# humidity.net
KiCad netlist of a schematic drawn in EAGLE
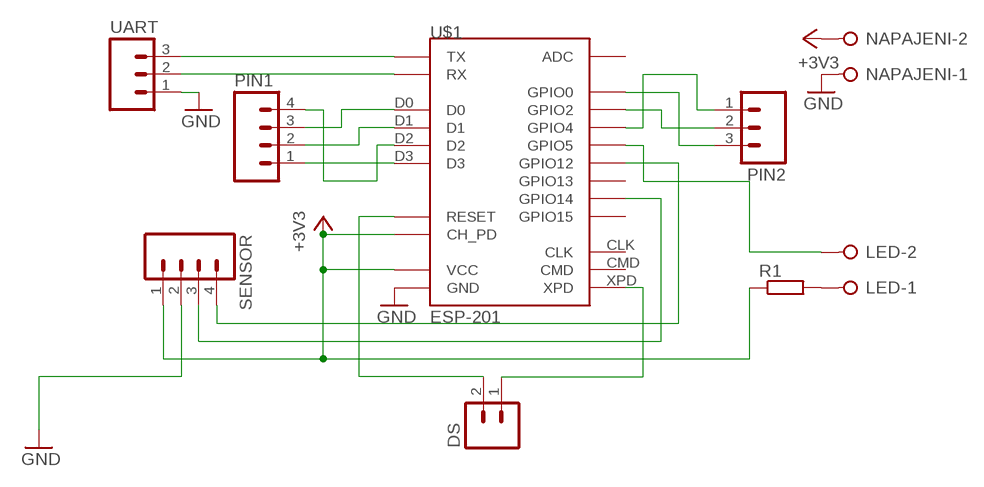
[diagram p0: schematic, sheet 1]

(export (version "E")
  (design (tool "Eeschema 10.0.6"))
  (components
    (comp (ref "DS")
      (value "M02")
      (footprint "eagle-import:02P")
      (libsource (lib "eagle-import") (part "M02"))
    )
    (comp (ref "LED")
      (value "W237-02P")
      (footprint "eagle-import:W237-132")
      (libsource (lib "eagle-import") (part "W237-02P"))
    )
    (comp (ref "NAPAJENI")
      (value "W237-02P")
      (footprint "eagle-import:W237-132")
      (libsource (lib "eagle-import") (part "W237-02P"))
    )
    (comp (ref "PIN1")
      (value "M04")
      (footprint "eagle-import:04P")
      (libsource (lib "eagle-import") (part "M04"))
    )
    (comp (ref "PIN2")
      (value "M03")
      (footprint "eagle-import:03P")
      (libsource (lib "eagle-import") (part "M03"))
    )
    (comp (ref "R1")
      (value "R-EU_0207/7")
      (footprint "eagle-import:0207_7")
      (libsource (lib "eagle-import") (part "R-EU_0207/7"))
    )
    (comp (ref "SENSOR")
      (value "M04")
      (footprint "eagle-import:04P")
      (libsource (lib "eagle-import") (part "M04"))
    )
    (comp (ref "U$1")
      (value "ESP-201")
      (footprint "eagle-import:ESP-201")
      (libsource (lib "eagle-import") (part "ESP-201"))
    )
    (comp (ref "UART")
      (value "M03")
      (footprint "eagle-import:03P")
      (libsource (lib "eagle-import") (part "M03"))
    )
  )
  (nets
    (net (code "1") (name "+3V3") (class "Default")
      (node (ref "NAPAJENI") (pin "2") (pinfunction "KL_2") (pintype "passive"))
      (node (ref "R1") (pin "1") (pinfunction "1_1") (pintype "passive"))
      (node (ref "SENSOR") (pin "1") (pinfunction "1_1") (pintype "passive"))
      (node (ref "U$1") (pin "3V3") (pinfunction "VCC_3V3") (pintype "bidirectional"))
      (node (ref "U$1") (pin "3V3_2") (pinfunction "VCC_3V3_2") (pintype "bidirectional"))
      (node (ref "U$1") (pin "3V3_3") (pinfunction "VCC_3V3_3") (pintype "bidirectional"))
      (node (ref "U$1") (pin "CH_PD") (pinfunction "CH_PD_CH_PD") (pintype "bidirectional"))
    )
    (net (code "2") (name "GND") (class "Default")
      (node (ref "NAPAJENI") (pin "1") (pinfunction "KL_1") (pintype "passive"))
      (node (ref "SENSOR") (pin "2") (pinfunction "2_2") (pintype "passive"))
      (node (ref "U$1") (pin "GND") (pinfunction "GND_GND") (pintype "bidirectional"))
      (node (ref "U$1") (pin "GND_2") (pinfunction "GND_GND_2") (pintype "bidirectional"))
      (node (ref "U$1") (pin "GND_3") (pinfunction "GND_GND_3") (pintype "bidirectional"))
      (node (ref "UART") (pin "1") (pinfunction "1_1") (pintype "passive"))
    )
    (net (code "3") (name "Net-(DS-Pad1)") (class "Default")
      (node (ref "DS") (pin "1") (pinfunction "1_1") (pintype "passive"))
      (node (ref "U$1") (pin "XPD") (pinfunction "XPD_XPD") (pintype "bidirectional"))
    )
    (net (code "4") (name "Net-(LEDA-KL)") (class "Default")
      (node (ref "LED") (pin "1") (pinfunction "KL_1") (pintype "passive"))
      (node (ref "R1") (pin "2") (pinfunction "2_2") (pintype "passive"))
    )
    (net (code "5") (name "Net-(LEDB-KL)") (class "Default")
      (node (ref "LED") (pin "2") (pinfunction "KL_2") (pintype "passive"))
      (node (ref "U$1") (pin "GPIO5") (pinfunction "GPIO5_GPIO5") (pintype "bidirectional"))
    )
    (net (code "6") (name "Net-(PIN1-Pad1)") (class "Default")
      (node (ref "PIN1") (pin "1") (pinfunction "1_1") (pintype "passive"))
      (node (ref "U$1") (pin "D3") (pinfunction "D3_D3") (pintype "bidirectional"))
    )
    (net (code "7") (name "Net-(PIN1-Pad2)") (class "Default")
      (node (ref "PIN1") (pin "2") (pinfunction "2_2") (pintype "passive"))
      (node (ref "U$1") (pin "D1") (pinfunction "D1_D1") (pintype "bidirectional"))
    )
    (net (code "8") (name "Net-(PIN1-Pad3)") (class "Default")
      (node (ref "PIN1") (pin "3") (pinfunction "3_3") (pintype "passive"))
      (node (ref "U$1") (pin "D0") (pinfunction "D0_D0") (pintype "bidirectional"))
    )
    (net (code "9") (name "Net-(PIN1-Pad4)") (class "Default")
      (node (ref "PIN1") (pin "4") (pinfunction "4_4") (pintype "passive"))
      (node (ref "U$1") (pin "D2") (pinfunction "D2_D2") (pintype "bidirectional"))
    )
    (net (code "10") (name "Net-(PIN2-Pad1)") (class "Default")
      (node (ref "PIN2") (pin "1") (pinfunction "1_1") (pintype "passive"))
      (node (ref "U$1") (pin "GPIO4") (pinfunction "GPIO4_GPIO4") (pintype "bidirectional"))
    )
    (net (code "11") (name "Net-(PIN2-Pad2)") (class "Default")
      (node (ref "PIN2") (pin "2") (pinfunction "2_2") (pintype "passive"))
      (node (ref "U$1") (pin "GPIO2") (pinfunction "GPIO2_GPIO2") (pintype "bidirectional"))
    )
    (net (code "12") (name "Net-(PIN2-Pad3)") (class "Default")
      (node (ref "PIN2") (pin "3") (pinfunction "3_3") (pintype "passive"))
      (node (ref "U$1") (pin "GPIO0") (pinfunction "GPIO0_GPIO0") (pintype "bidirectional"))
    )
    (net (code "13") (name "Net-(SENSOR-Pad3)") (class "Default")
      (node (ref "SENSOR") (pin "3") (pinfunction "3_3") (pintype "passive"))
      (node (ref "U$1") (pin "GPIO14") (pinfunction "GPIO14_GPIO14") (pintype "bidirectional"))
    )
    (net (code "14") (name "Net-(SENSOR-Pad4)") (class "Default")
      (node (ref "SENSOR") (pin "4") (pinfunction "4_4") (pintype "passive"))
      (node (ref "U$1") (pin "GPIO12") (pinfunction "GPIO12_GPIO12") (pintype "bidirectional"))
    )
    (net (code "15") (name "Net-(U$1-PadRX)") (class "Default")
      (node (ref "U$1") (pin "RX") (pinfunction "RX_RX") (pintype "bidirectional"))
      (node (ref "UART") (pin "2") (pinfunction "2_2") (pintype "passive"))
    )
    (net (code "16") (name "Net-(U$1-PadTX)") (class "Default")
      (node (ref "U$1") (pin "TX") (pinfunction "TX_TX") (pintype "bidirectional"))
      (node (ref "UART") (pin "3") (pinfunction "3_3") (pintype "passive"))
    )
    (net (code "17") (name "Net-(U$1-RESET)") (class "Default")
      (node (ref "DS") (pin "2") (pinfunction "2_2") (pintype "passive"))
      (node (ref "U$1") (pin "RST") (pinfunction "RESET_RST") (pintype "bidirectional"))
    )
    (net (code "18") (name "unconnected-(U$1-PadADC)") (class "Default")
      (node (ref "U$1") (pin "ADC") (pinfunction "ADC_ADC") (pintype "bidirectional"))
    )
    (net (code "19") (name "unconnected-(U$1-PadCLK)") (class "Default")
      (node (ref "U$1") (pin "CLK") (pinfunction "CLK_CLK") (pintype "bidirectional"))
    )
    (net (code "20") (name "unconnected-(U$1-PadCMD)") (class "Default")
      (node (ref "U$1") (pin "CMD") (pinfunction "CMD_CMD") (pintype "bidirectional"))
    )
    (net (code "21") (name "unconnected-(U$1-PadGPIO13)") (class "Default")
      (node (ref "U$1") (pin "GPIO13") (pinfunction "GPIO13_GPIO13") (pintype "bidirectional"))
    )
    (net (code "22") (name "unconnected-(U$1-PadGPIO15)") (class "Default")
      (node (ref "U$1") (pin "GPIO15") (pinfunction "GPIO15_GPIO15") (pintype "bidirectional"))
    )
  )
)
